# CAN-to-CAN.net
KiCad netlist of a schematic drawn in Altium Designer
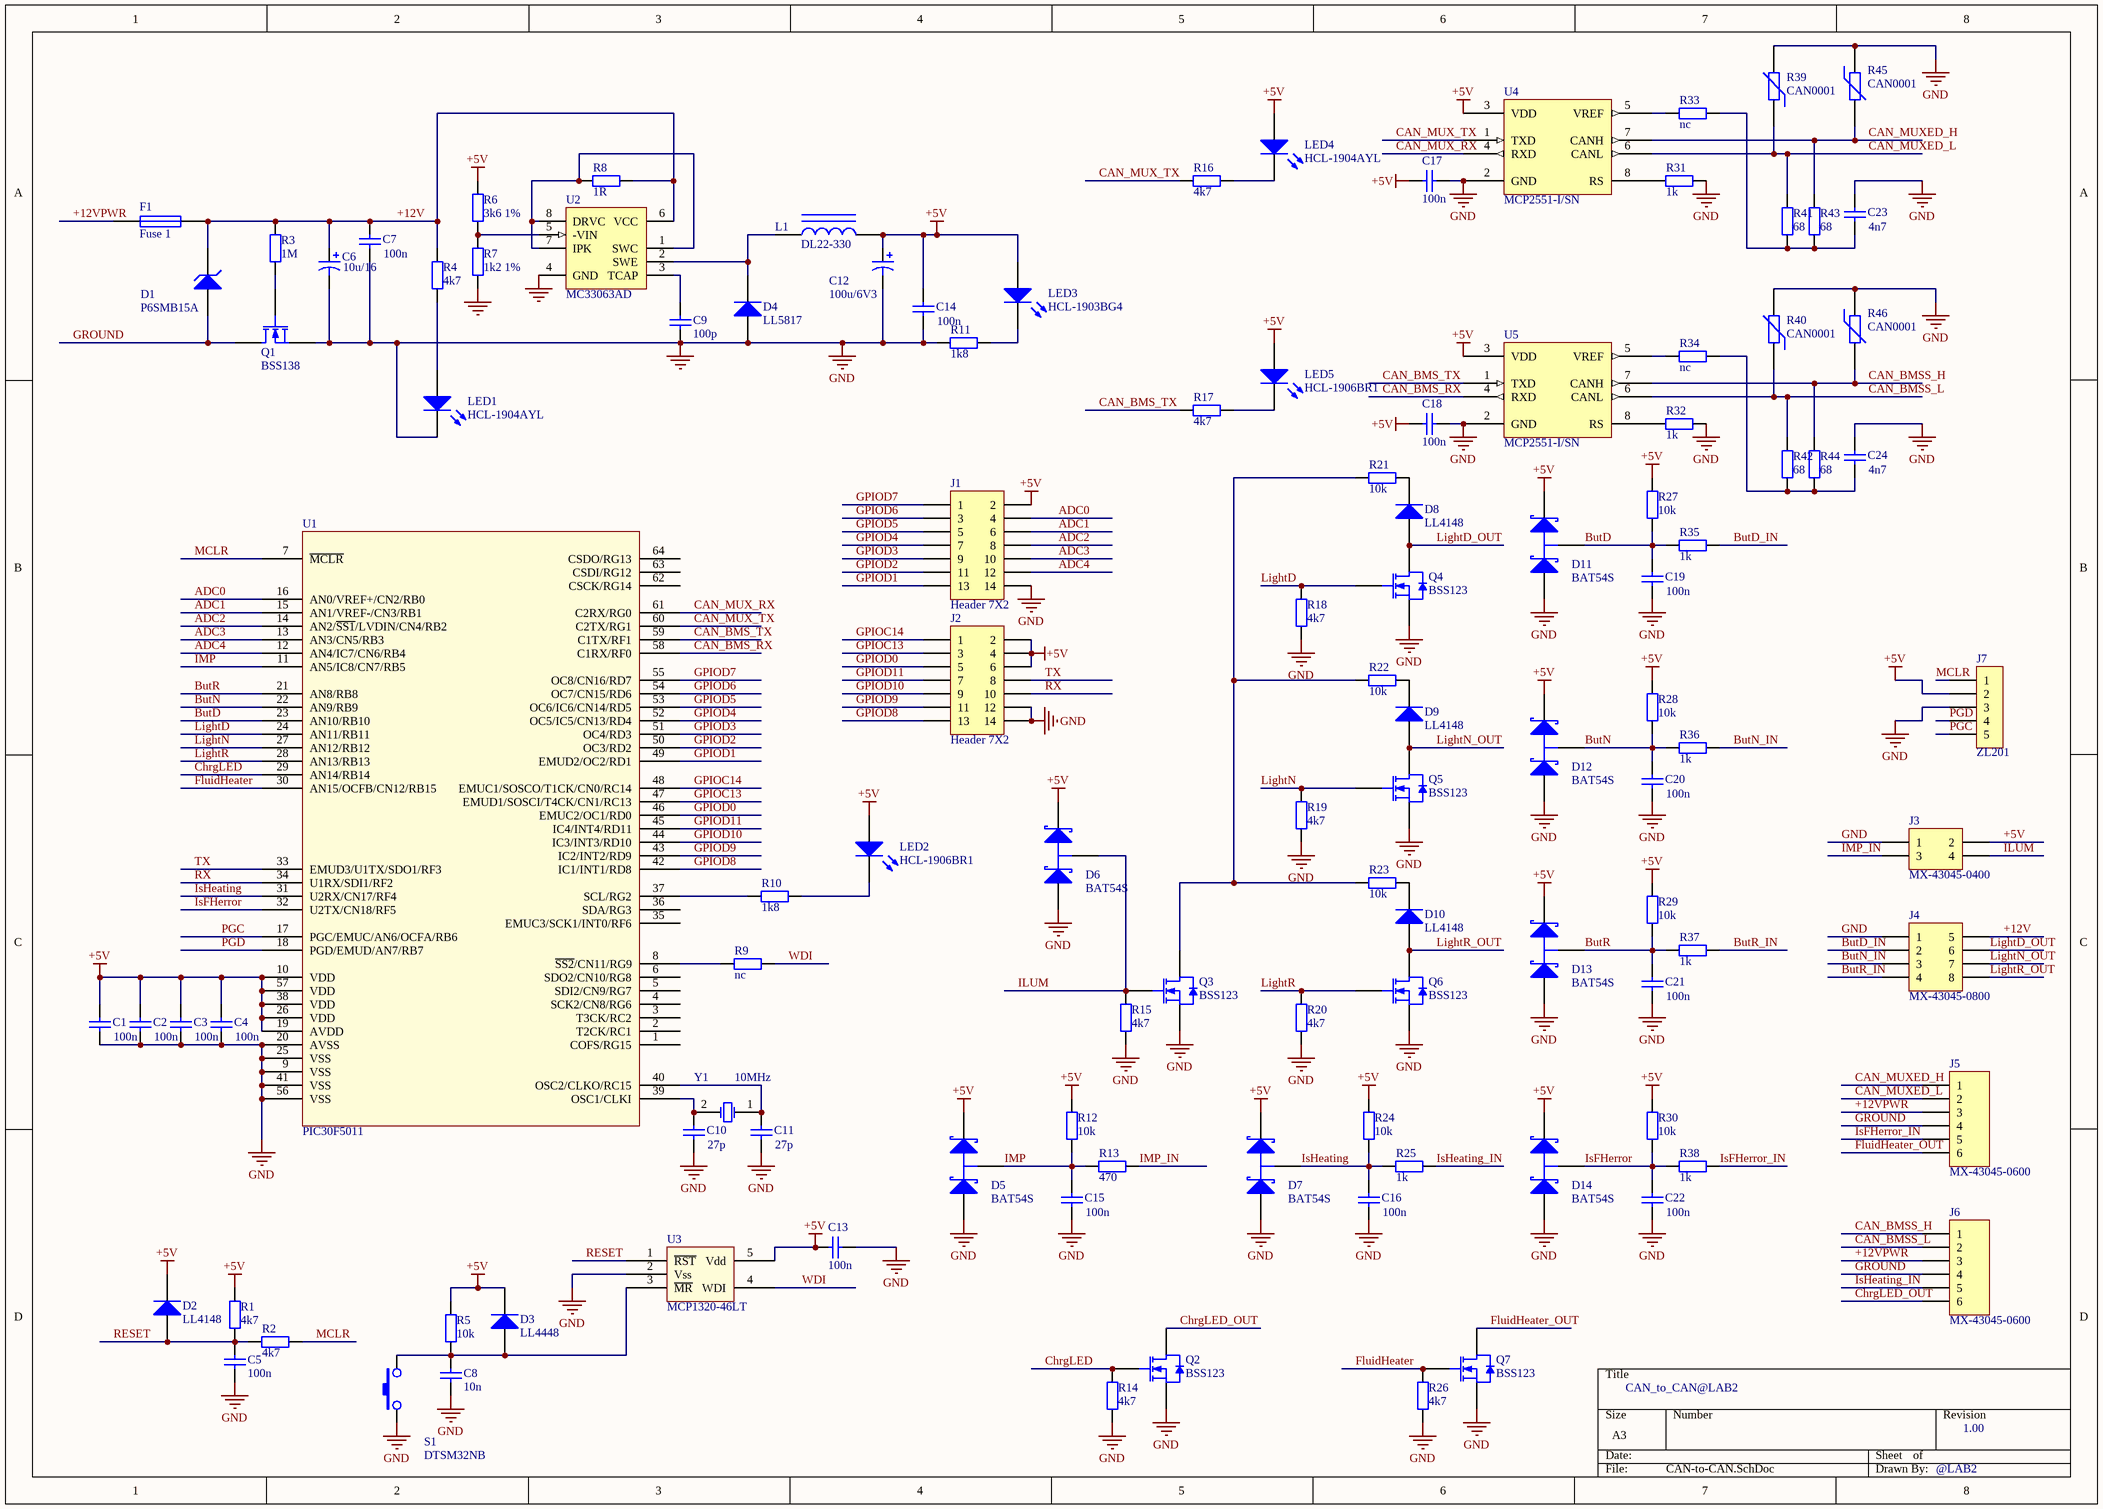
[diagram p0: CAN-to-CAN.SchDoc]

(export (version "E")
  (design (tool "Eeschema 10.0.6"))
  (components
    (comp (ref "C1")
      (value "100n")
      (footprint "0603")
      (description "Capacitor")
      (libsource (lib "Miscellaneous Devices") (part "Cap"))
    )
    (comp (ref "C2")
      (value "100n")
      (footprint "0603")
      (description "Capacitor")
      (libsource (lib "Miscellaneous Devices") (part "Cap"))
    )
    (comp (ref "C3")
      (value "100n")
      (footprint "0603")
      (description "Capacitor")
      (libsource (lib "Miscellaneous Devices") (part "Cap"))
    )
    (comp (ref "C4")
      (value "100n")
      (footprint "0603")
      (description "Capacitor")
      (libsource (lib "Miscellaneous Devices") (part "Cap"))
    )
    (comp (ref "C5")
      (value "100n")
      (footprint "0603")
      (description "Capacitor")
      (libsource (lib "Miscellaneous Devices") (part "Cap"))
    )
    (comp (ref "C6")
      (value "10u/16")
      (footprint "1608[0603]")
      (description "Polarized Capacitor (Radial)")
      (libsource (lib "Miscellaneous Devices") (part "Cap Pol1"))
    )
    (comp (ref "C7")
      (value "100n")
      (footprint "1812")
      (description "Capacitor")
      (libsource (lib "Miscellaneous Devices") (part "Cap"))
    )
    (comp (ref "C8")
      (value "10n")
      (footprint "0603")
      (description "Capacitor")
      (libsource (lib "Miscellaneous Devices") (part "Cap"))
    )
    (comp (ref "C9")
      (value "100p")
      (footprint "0603")
      (description "Capacitor")
      (libsource (lib "Miscellaneous Devices") (part "Cap"))
    )
    (comp (ref "C10")
      (value "27p")
      (footprint "0603")
      (description "Capacitor")
      (libsource (lib "Miscellaneous Devices") (part "Cap"))
    )
    (comp (ref "C11")
      (value "27p")
      (footprint "0603")
      (description "Capacitor")
      (libsource (lib "Miscellaneous Devices") (part "Cap"))
    )
    (comp (ref "C12")
      (value "100u/6V3")
      (footprint "0402")
      (description "Polarized Capacitor (Radial)")
      (libsource (lib "Miscellaneous Devices") (part "Cap Pol1"))
    )
    (comp (ref "C13")
      (value "100n")
      (footprint "0603")
      (description "Capacitor")
      (libsource (lib "Miscellaneous Devices") (part "Cap"))
    )
    (comp (ref "C14")
      (value "100n")
      (footprint "0603")
      (description "Capacitor")
      (libsource (lib "Miscellaneous Devices") (part "Cap"))
    )
    (comp (ref "C15")
      (value "100n")
      (footprint "0603")
      (description "Capacitor")
      (libsource (lib "Miscellaneous Devices") (part "Cap"))
    )
    (comp (ref "C16")
      (value "100n")
      (footprint "0603")
      (description "Capacitor")
      (libsource (lib "Miscellaneous Devices") (part "Cap"))
    )
    (comp (ref "C17")
      (value "100n")
      (footprint "0603")
      (description "Capacitor")
      (libsource (lib "Miscellaneous Devices") (part "Cap"))
    )
    (comp (ref "C18")
      (value "100n")
      (footprint "0603")
      (description "Capacitor")
      (libsource (lib "Miscellaneous Devices") (part "Cap"))
    )
    (comp (ref "C19")
      (value "100n")
      (footprint "0603")
      (description "Capacitor")
      (libsource (lib "Miscellaneous Devices") (part "Cap"))
    )
    (comp (ref "C20")
      (value "100n")
      (footprint "0603")
      (description "Capacitor")
      (libsource (lib "Miscellaneous Devices") (part "Cap"))
    )
    (comp (ref "C21")
      (value "100n")
      (footprint "0603")
      (description "Capacitor")
      (libsource (lib "Miscellaneous Devices") (part "Cap"))
    )
    (comp (ref "C22")
      (value "100n")
      (footprint "0603")
      (description "Capacitor")
      (libsource (lib "Miscellaneous Devices") (part "Cap"))
    )
    (comp (ref "C23")
      (value "4n7")
      (footprint "0603")
      (description "Capacitor")
      (libsource (lib "Miscellaneous Devices") (part "Cap"))
    )
    (comp (ref "C24")
      (value "4n7")
      (footprint "0603")
      (description "Capacitor")
      (libsource (lib "Miscellaneous Devices") (part "Cap"))
    )
    (comp (ref "D1")
      (value "P6SMB15A")
      (footprint "SMB")
      (description "Zener Diode")
      (libsource (lib "Miscellaneous Devices") (part "D Zener"))
    )
    (comp (ref "D2")
      (value "LL4148")
      (footprint "DIODE-0.4")
      (description "High Conductance Fast Diode")
      (libsource (lib "FSC Discrete Diode") (part "1N4148"))
    )
    (comp (ref "D3")
      (value "LL4448")
      (footprint "DIODE_SMC")
      (description "Default Diode")
      (libsource (lib "Miscellaneous Devices") (part "Diode"))
    )
    (comp (ref "D4")
      (value "LL5817")
      (footprint "DIODE-0.7")
      (description "High Conductance Fast Diode")
      (libsource (lib "FSC Discrete Diode") (part "1N4148"))
    )
    (comp (ref "D5")
      (value "BAT54S")
      (footprint "DO-35")
      (description "Schottky Barrier Double Diode")
      (libsource (lib "Philips Discrete Diode - Schottky") (part "BAT54S"))
    )
    (comp (ref "D6")
      (value "BAT54S")
      (footprint "DO-41")
      (description "Schottky Barrier Double Diode")
      (libsource (lib "Philips Discrete Diode - Schottky") (part "BAT54S"))
    )
    (comp (ref "D7")
      (value "BAT54S")
      (footprint "DO-204AL")
      (description "Schottky Barrier Double Diode")
      (libsource (lib "Philips Discrete Diode - Schottky") (part "BAT54S"))
    )
    (comp (ref "D8")
      (value "LL4148")
      (footprint "DO-201AD")
      (description "High Conductance Fast Diode")
      (libsource (lib "FSC Discrete Diode") (part "1N4148"))
    )
    (comp (ref "D9")
      (value "LL4148")
      (footprint "DIODE-0.4")
      (description "High Conductance Fast Diode")
      (libsource (lib "FSC Discrete Diode") (part "1N4148"))
    )
    (comp (ref "D10")
      (value "LL4148")
      (footprint "DO-7")
      (description "High Conductance Fast Diode")
      (libsource (lib "FSC Discrete Diode") (part "1N4148"))
    )
    (comp (ref "D11")
      (value "BAT54S")
      (footprint "DO-41")
      (description "Schottky Barrier Double Diode")
      (libsource (lib "Philips Discrete Diode - Schottky") (part "BAT54S"))
    )
    (comp (ref "D12")
      (value "BAT54S")
      (footprint "DO-201AD")
      (description "Schottky Barrier Double Diode")
      (libsource (lib "Philips Discrete Diode - Schottky") (part "BAT54S"))
    )
    (comp (ref "D13")
      (value "BAT54S")
      (footprint "DO-201AD")
      (description "Schottky Barrier Double Diode")
      (libsource (lib "Philips Discrete Diode - Schottky") (part "BAT54S"))
    )
    (comp (ref "D14")
      (value "BAT54S")
      (footprint "DO-41")
      (description "Schottky Barrier Double Diode")
      (libsource (lib "Philips Discrete Diode - Schottky") (part "BAT54S"))
    )
    (comp (ref "F1")
      (value "Fuse 1")
      (footprint "1812")
      (description "Fuse")
      (libsource (lib "Miscellaneous Devices") (part "Fuse 1"))
    )
    (comp (ref "J1")
      (value "Header 7X2")
      (footprint "HDR2X7")
      (description "Header, 7-Pin, Dual row")
      (libsource (lib "Miscellaneous Connectors") (part "Header 7X2"))
    )
    (comp (ref "J2")
      (value "Header 7X2")
      (footprint "HDR2X7")
      (description "Header, 7-Pin, Dual row")
      (libsource (lib "Miscellaneous Connectors") (part "Header 7X2"))
    )
    (comp (ref "J3")
      (value "MX-43045-0400")
      (footprint "SOT223_N")
      (description "Header, 2-Pin, Dual row")
      (libsource (lib "Miscellaneous Connectors") (part "Header 2X2"))
    )
    (comp (ref "J4")
      (value "MX-43045-0800")
      (footprint "DIP-8")
      (description "Header, 4-Pin, Dual row")
      (libsource (lib "Miscellaneous Connectors") (part "Header 4X2A"))
    )
    (comp (ref "J5")
      (value "MX-43045-0600")
      (footprint "DPDT-6")
      (description "Header, 6-Pin")
      (libsource (lib "Miscellaneous Connectors") (part "Header 6"))
    )
    (comp (ref "J6")
      (value "MX-43045-0600")
      (footprint "DPDT-6")
      (description "Header, 6-Pin")
      (libsource (lib "Miscellaneous Connectors") (part "Header 6"))
    )
    (comp (ref "J7")
      (value "ZL201")
      (footprint "HDR1X5")
      (description "Connector")
      (libsource (lib "*") (part "CON5"))
    )
    (comp (ref "L1")
      (value "DL22-330")
      (footprint "0603")
      (description "Magnetic-Core Inductor")
      (libsource (lib "Miscellaneous Devices") (part "Inductor Iron"))
    )
    (comp (ref "LED1")
      (value "HCL-1904AYL")
      (footprint "0603")
      (description "Typical BLUE SiC LED")
      (libsource (lib "Miscellaneous Devices") (part "LED3"))
    )
    (comp (ref "LED2")
      (value "HCL-1906BR1")
      (footprint "0603")
      (description "Typical BLUE SiC LED")
      (libsource (lib "Miscellaneous Devices") (part "LED3"))
    )
    (comp (ref "LED3")
      (value "HCL-1903BG4")
      (footprint "0603")
      (description "Typical BLUE SiC LED")
      (libsource (lib "Miscellaneous Devices") (part "LED3"))
    )
    (comp (ref "LED4")
      (value "HCL-1904AYL")
      (footprint "0603")
      (description "Typical BLUE SiC LED")
      (libsource (lib "Miscellaneous Devices") (part "LED3"))
    )
    (comp (ref "LED5")
      (value "HCL-1906BR1")
      (footprint "0603")
      (description "Typical BLUE SiC LED")
      (libsource (lib "Miscellaneous Devices") (part "LED3"))
    )
    (comp (ref "Q1")
      (value "BSS138")
      (footprint "SOT89L")
      (description "N-Channel Enhancement Mode Vertical DMOS FET")
      (libsource (lib "Zetex Discrete MOSFET") (part "BSS138"))
    )
    (comp (ref "Q2")
      (value "BSS123")
      (footprint "SOT23_M")
      (description "N-channel Enhancement Mode Vertical D-MOSFET")
      (libsource (lib "Philips Discrete MOSFET - Low Power") (part "BSS123"))
    )
    (comp (ref "Q3")
      (value "BSS123")
      (footprint "SOT23_M")
      (description "N-channel Enhancement Mode Vertical D-MOSFET")
      (libsource (lib "Philips Discrete MOSFET - Low Power") (part "BSS123"))
    )
    (comp (ref "Q4")
      (value "BSS123")
      (footprint "SOT89L")
      (description "N-channel Enhancement Mode Vertical D-MOSFET")
      (libsource (lib "Philips Discrete MOSFET - Low Power") (part "BSS123"))
    )
    (comp (ref "Q5")
      (value "BSS123")
      (footprint "DIP-P8")
      (description "N-channel Enhancement Mode Vertical D-MOSFET")
      (libsource (lib "Philips Discrete MOSFET - Low Power") (part "BSS123"))
    )
    (comp (ref "Q6")
      (value "BSS123")
      (footprint "DIODE_SMC")
      (description "N-channel Enhancement Mode Vertical D-MOSFET")
      (libsource (lib "Philips Discrete MOSFET - Low Power") (part "BSS123"))
    )
    (comp (ref "Q7")
      (value "BSS123")
      (footprint "SOT89N")
      (description "N-channel Enhancement Mode Vertical D-MOSFET")
      (libsource (lib "Philips Discrete MOSFET - Low Power") (part "BSS123"))
    )
    (comp (ref "R1")
      (value "4k7")
      (footprint "0603")
      (description "Resistor")
      (libsource (lib "Miscellaneous Devices") (part "Res2"))
    )
    (comp (ref "R2")
      (value "4k7")
      (footprint "0603")
      (description "Resistor")
      (libsource (lib "") (part "Res2_2"))
    )
    (comp (ref "R3")
      (value "1M")
      (footprint "6-0805_L")
      (description "Resistor")
      (libsource (lib "Miscellaneous Devices") (part "Res2"))
    )
    (comp (ref "R4")
      (value "4k7")
      (footprint "6-0805_N")
      (description "Resistor")
      (libsource (lib "Miscellaneous Devices") (part "Res2"))
    )
    (comp (ref "R5")
      (value "10k")
      (footprint "0603")
      (description "Resistor")
      (libsource (lib "") (part "Res2_3"))
    )
    (comp (ref "R6")
      (value "3k6 1%")
      (footprint "0603")
      (description "Resistor")
      (libsource (lib "Miscellaneous Devices") (part "Res2"))
    )
    (comp (ref "R7")
      (value "1k2 1%")
      (footprint "0603")
      (description "Resistor")
      (libsource (lib "") (part "Res2_3"))
    )
    (comp (ref "R8")
      (value "1R")
      (footprint "6-0805_L")
      (description "Resistor")
      (libsource (lib "") (part "Res2_1"))
    )
    (comp (ref "R9")
      (value "nc")
      (footprint "0603")
      (description "Resistor")
      (libsource (lib "") (part "Res2_2"))
    )
    (comp (ref "R10")
      (value "1k8")
      (footprint "0603")
      (description "Resistor")
      (libsource (lib "") (part "Res2_2"))
    )
    (comp (ref "R11")
      (value "1k8")
      (footprint "0603")
      (description "Resistor")
      (libsource (lib "") (part "Res2_2"))
    )
    (comp (ref "R12")
      (value "10k")
      (footprint "0603")
      (description "Resistor")
      (libsource (lib "Miscellaneous Devices") (part "Res2"))
    )
    (comp (ref "R13")
      (value "470")
      (footprint "0603")
      (description "Resistor")
      (libsource (lib "") (part "Res2_2"))
    )
    (comp (ref "R14")
      (value "4k7")
      (footprint "0603")
      (description "Resistor")
      (libsource (lib "Miscellaneous Devices") (part "Res2"))
    )
    (comp (ref "R15")
      (value "4k7")
      (footprint "0603")
      (description "Resistor")
      (libsource (lib "Miscellaneous Devices") (part "Res2"))
    )
    (comp (ref "R16")
      (value "4k7")
      (footprint "0603")
      (description "Resistor")
      (libsource (lib "") (part "Res2_2"))
    )
    (comp (ref "R17")
      (value "4k7")
      (footprint "0603")
      (description "Resistor")
      (libsource (lib "") (part "Res2_2"))
    )
    (comp (ref "R18")
      (value "4k7")
      (footprint "0603")
      (description "Resistor")
      (libsource (lib "Miscellaneous Devices") (part "Res2"))
    )
    (comp (ref "R19")
      (value "4k7")
      (footprint "0603")
      (description "Resistor")
      (libsource (lib "Miscellaneous Devices") (part "Res2"))
    )
    (comp (ref "R20")
      (value "4k7")
      (footprint "0603")
      (description "Resistor")
      (libsource (lib "Miscellaneous Devices") (part "Res2"))
    )
    (comp (ref "R21")
      (value "10k")
      (footprint "0603")
      (description "Resistor")
      (libsource (lib "") (part "Res2_1"))
    )
    (comp (ref "R22")
      (value "10k")
      (footprint "0603")
      (description "Resistor")
      (libsource (lib "") (part "Res2_1"))
    )
    (comp (ref "R23")
      (value "10k")
      (footprint "0603")
      (description "Resistor")
      (libsource (lib "") (part "Res2_1"))
    )
    (comp (ref "R24")
      (value "10k")
      (footprint "0603")
      (description "Resistor")
      (libsource (lib "Miscellaneous Devices") (part "Res2"))
    )
    (comp (ref "R25")
      (value "1k")
      (footprint "0603")
      (description "Resistor")
      (libsource (lib "") (part "Res2_2"))
    )
    (comp (ref "R26")
      (value "4k7")
      (footprint "0603")
      (description "Resistor")
      (libsource (lib "Miscellaneous Devices") (part "Res2"))
    )
    (comp (ref "R27")
      (value "10k")
      (footprint "0603")
      (description "Resistor")
      (libsource (lib "Miscellaneous Devices") (part "Res2"))
    )
    (comp (ref "R28")
      (value "10k")
      (footprint "0603")
      (description "Resistor")
      (libsource (lib "Miscellaneous Devices") (part "Res2"))
    )
    (comp (ref "R29")
      (value "10k")
      (footprint "0603")
      (description "Resistor")
      (libsource (lib "Miscellaneous Devices") (part "Res2"))
    )
    (comp (ref "R30")
      (value "10k")
      (footprint "0603")
      (description "Resistor")
      (libsource (lib "Miscellaneous Devices") (part "Res2"))
    )
    (comp (ref "R31")
      (value "1k")
      (footprint "0603")
      (description "Resistor")
      (libsource (lib "") (part "Res2_1"))
    )
    (comp (ref "R32")
      (value "1k")
      (footprint "0603")
      (description "Resistor")
      (libsource (lib "") (part "Res2_1"))
    )
    (comp (ref "R33")
      (value "nc")
      (footprint "0603")
      (description "Resistor")
      (libsource (lib "") (part "Res2_1"))
    )
    (comp (ref "R34")
      (value "nc")
      (footprint "0603")
      (description "Resistor")
      (libsource (lib "") (part "Res2_1"))
    )
    (comp (ref "R35")
      (value "1k")
      (footprint "0603")
      (description "Resistor")
      (libsource (lib "") (part "Res2_2"))
    )
    (comp (ref "R36")
      (value "1k")
      (footprint "0603")
      (description "Resistor")
      (libsource (lib "") (part "Res2_2"))
    )
    (comp (ref "R37")
      (value "1k")
      (footprint "0603")
      (description "Resistor")
      (libsource (lib "") (part "Res2_2"))
    )
    (comp (ref "R38")
      (value "1k")
      (footprint "0603")
      (description "Resistor")
      (libsource (lib "") (part "Res2_2"))
    )
    (comp (ref "R39")
      (value "CAN0001")
      (footprint "0603")
      (description "Varistor (Voltage-Sensitive Resistor)")
      (libsource (lib "Miscellaneous Devices") (part "Res Varistor"))
    )
    (comp (ref "R40")
      (value "CAN0001")
      (footprint "0603")
      (description "Varistor (Voltage-Sensitive Resistor)")
      (libsource (lib "Miscellaneous Devices") (part "Res Varistor"))
    )
    (comp (ref "R41")
      (value "68")
      (footprint "0603")
      (description "Resistor")
      (libsource (lib "Miscellaneous Devices") (part "Res2"))
    )
    (comp (ref "R42")
      (value "68")
      (footprint "0603")
      (description "Resistor")
      (libsource (lib "Miscellaneous Devices") (part "Res2"))
    )
    (comp (ref "R43")
      (value "68")
      (footprint "0603")
      (description "Resistor")
      (libsource (lib "Miscellaneous Devices") (part "Res2"))
    )
    (comp (ref "R44")
      (value "68")
      (footprint "0603")
      (description "Resistor")
      (libsource (lib "Miscellaneous Devices") (part "Res2"))
    )
    (comp (ref "R45")
      (value "CAN0001")
      (footprint "0603")
      (description "Varistor (Voltage-Sensitive Resistor)")
      (libsource (lib "Miscellaneous Devices") (part "Res Varistor"))
    )
    (comp (ref "R46")
      (value "CAN0001")
      (footprint "0603")
      (description "Varistor (Voltage-Sensitive Resistor)")
      (libsource (lib "Miscellaneous Devices") (part "Res Varistor"))
    )
    (comp (ref "S1")
      (value "DTSM32NB")
      (footprint "PIN-W2/E2.8")
      (description "Switch PushButton")
      (libsource (lib "*") (part "PUSHB"))
    )
    (comp (ref "U1")
      (value "PIC30F5011")
      (footprint "TQFP-64_L")
      (description "PIC30F5011 - Up")
      (libsource (lib "AD Microcontroller ARM") (part "PIC30F5011"))
    )
    (comp (ref "U2")
      (value "MC33063AD")
      (footprint "SO8_N")
      (description "DC-to-DC Converter Control Circuit")
      (libsource (lib "Motorola Power Mgt DC-DC Converter") (part "MC33063AD"))
    )
    (comp (ref "U3")
      (value "MCP1320-46LT")
      (footprint "MODULE5B")
      (libsource (lib "X-Tro's Misc") (part "MCP1320"))
    )
    (comp (ref "U4")
      (value "MCP2551-I/SN")
      (footprint "DB008_L")
      (description "High Speed CAN Transceiver, 8-Pin Plastic SOIC, Industrial Grade")
      (libsource (lib "Microchip Interface Line Transceiver") (part "MCP2551-I/SN"))
    )
    (comp (ref "U5")
      (value "MCP2551-I/SN")
      (footprint "DIP-8")
      (description "High Speed CAN Transceiver, 8-Pin Plastic SOIC, Industrial Grade")
      (libsource (lib "Microchip Interface Line Transceiver") (part "MCP2551-I/SN"))
    )
    (comp (ref "Y1")
      (value "10MHz")
      (footprint "SPST-2")
      (description "Crystal Oscillator")
      (libsource (lib "Miscellaneous Devices") (part "XTAL"))
    )
  )
  (nets
    (net (code "1") (name "+5V") (class "Default")
      (node (ref "C1") (pin "1") (pinfunction "1_1") (pintype "passive"))
      (node (ref "C12") (pin "1") (pinfunction "1_1") (pintype "passive"))
      (node (ref "C13") (pin "1") (pinfunction "1_1") (pintype "passive"))
      (node (ref "C14") (pin "1") (pinfunction "1_1") (pintype "passive"))
      (node (ref "C17") (pin "1") (pinfunction "1_1") (pintype "passive"))
      (node (ref "C18") (pin "1") (pinfunction "1_1") (pintype "passive"))
      (node (ref "C2") (pin "1") (pinfunction "1_1") (pintype "passive"))
      (node (ref "C3") (pin "1") (pinfunction "1_1") (pintype "passive"))
      (node (ref "C4") (pin "1") (pinfunction "1_1") (pintype "passive"))
      (node (ref "D11") (pin "2") (pinfunction "K_2") (pintype "passive"))
      (node (ref "D12") (pin "2") (pinfunction "K_2") (pintype "passive"))
      (node (ref "D13") (pin "2") (pinfunction "K_2") (pintype "passive"))
      (node (ref "D14") (pin "2") (pinfunction "K_2") (pintype "passive"))
      (node (ref "D2") (pin "2") (pinfunction "K_2") (pintype "passive"))
      (node (ref "D3") (pin "2") (pinfunction "K_2") (pintype "passive"))
      (node (ref "D5") (pin "2") (pinfunction "K_2") (pintype "passive"))
      (node (ref "D6") (pin "2") (pinfunction "K_2") (pintype "passive"))
      (node (ref "D7") (pin "2") (pinfunction "K_2") (pintype "passive"))
      (node (ref "J1") (pin "2") (pinfunction "2_2") (pintype "passive"))
      (node (ref "J2") (pin "2") (pinfunction "2_2") (pintype "passive"))
      (node (ref "J2") (pin "4") (pinfunction "4_4") (pintype "passive"))
      (node (ref "J2") (pin "6") (pinfunction "6_6") (pintype "passive"))
      (node (ref "J3") (pin "2") (pinfunction "2_2") (pintype "passive"))
      (node (ref "J7") (pin "2") (pinfunction "2_2") (pintype "passive"))
      (node (ref "L1") (pin "2") (pinfunction "2_2") (pintype "passive"))
      (node (ref "LED2") (pin "1") (pinfunction "A_1") (pintype "passive"))
      (node (ref "LED3") (pin "1") (pinfunction "A_1") (pintype "passive"))
      (node (ref "LED4") (pin "1") (pinfunction "A_1") (pintype "passive"))
      (node (ref "LED5") (pin "1") (pinfunction "A_1") (pintype "passive"))
      (node (ref "R1") (pin "1") (pinfunction "1_1") (pintype "passive"))
      (node (ref "R12") (pin "1") (pinfunction "1_1") (pintype "passive"))
      (node (ref "R24") (pin "1") (pinfunction "1_1") (pintype "passive"))
      (node (ref "R27") (pin "1") (pinfunction "1_1") (pintype "passive"))
      (node (ref "R28") (pin "1") (pinfunction "1_1") (pintype "passive"))
      (node (ref "R29") (pin "1") (pinfunction "1_1") (pintype "passive"))
      (node (ref "R30") (pin "1") (pinfunction "1_1") (pintype "passive"))
      (node (ref "R5") (pin "2") (pinfunction "2_2") (pintype "passive"))
      (node (ref "R6") (pin "1") (pinfunction "1_1") (pintype "passive"))
      (node (ref "U1") (pin "10") (pinfunction "VDD_10") (pintype "passive"))
      (node (ref "U1") (pin "19") (pinfunction "AVDD_19") (pintype "passive"))
      (node (ref "U1") (pin "26") (pinfunction "VDD_26") (pintype "passive"))
      (node (ref "U1") (pin "38") (pinfunction "VDD_38") (pintype "passive"))
      (node (ref "U1") (pin "57") (pinfunction "VDD_57") (pintype "passive"))
      (node (ref "U3") (pin "5") (pinfunction "Vdd_5") (pintype "passive"))
      (node (ref "U4") (pin "3") (pinfunction "VDD_3") (pintype "power_in"))
      (node (ref "U5") (pin "3") (pinfunction "VDD_3") (pintype "power_in"))
    )
    (net (code "2") (name "/+12V") (class "Default")
      (node (ref "C6") (pin "1") (pinfunction "1_1") (pintype "passive"))
      (node (ref "C7") (pin "1") (pinfunction "1_1") (pintype "passive"))
      (node (ref "D1") (pin "2") (pinfunction "K_2") (pintype "passive"))
      (node (ref "F1") (pin "2") (pinfunction "2_2") (pintype "passive"))
      (node (ref "J4") (pin "5") (pinfunction "5_5") (pintype "passive"))
      (node (ref "R3") (pin "1") (pinfunction "1_1") (pintype "passive"))
      (node (ref "R4") (pin "1") (pinfunction "1_1") (pintype "passive"))
      (node (ref "R8") (pin "2") (pinfunction "2_2") (pintype "passive"))
      (node (ref "U2") (pin "6") (pinfunction "VCC_6") (pintype "power_in"))
    )
    (net (code "3") (name "/+12VPWR") (class "Default")
      (node (ref "F1") (pin "1") (pinfunction "1_1") (pintype "passive"))
      (node (ref "J5") (pin "3") (pinfunction "3_3") (pintype "passive"))
      (node (ref "J6") (pin "3") (pinfunction "3_3") (pintype "passive"))
    )
    (net (code "4") (name "/ADC0") (class "Default")
      (node (ref "J1") (pin "4") (pinfunction "4_4") (pintype "passive"))
      (node (ref "U1") (pin "16") (pinfunction "AN0/VREF+/CN2/RB0_16") (pintype "passive"))
    )
    (net (code "5") (name "/ADC1") (class "Default")
      (node (ref "J1") (pin "6") (pinfunction "6_6") (pintype "passive"))
      (node (ref "U1") (pin "15") (pinfunction "AN1/VREF-/CN3/RB1_15") (pintype "passive"))
    )
    (net (code "6") (name "/ADC2") (class "Default")
      (node (ref "J1") (pin "8") (pinfunction "8_8") (pintype "passive"))
      (node (ref "U1") (pin "14") (pinfunction "AN2/~{SS1}/LVDIN/CN4/RB2_14") (pintype "passive"))
    )
    (net (code "7") (name "/ADC3") (class "Default")
      (node (ref "J1") (pin "10") (pinfunction "10_10") (pintype "passive"))
      (node (ref "U1") (pin "13") (pinfunction "AN3/CN5/RB3_13") (pintype "passive"))
    )
    (net (code "8") (name "/ADC4") (class "Default")
      (node (ref "J1") (pin "12") (pinfunction "12_12") (pintype "passive"))
      (node (ref "U1") (pin "12") (pinfunction "AN4/IC7/CN6/RB4_12") (pintype "passive"))
    )
    (net (code "9") (name "/ButD") (class "Default")
      (node (ref "C19") (pin "1") (pinfunction "1_1") (pintype "passive"))
      (node (ref "D11") (pin "3") (pinfunction "C_3") (pintype "passive"))
      (node (ref "R27") (pin "2") (pinfunction "2_2") (pintype "passive"))
      (node (ref "R35") (pin "2") (pinfunction "2_2") (pintype "passive"))
      (node (ref "U1") (pin "23") (pinfunction "AN10/RB10_23") (pintype "passive"))
    )
    (net (code "10") (name "/ButD_IN") (class "Default")
      (node (ref "J4") (pin "2") (pinfunction "2_2") (pintype "passive"))
      (node (ref "R35") (pin "1") (pinfunction "1_1") (pintype "passive"))
    )
    (net (code "11") (name "/ButN") (class "Default")
      (node (ref "C20") (pin "1") (pinfunction "1_1") (pintype "passive"))
      (node (ref "D12") (pin "3") (pinfunction "C_3") (pintype "passive"))
      (node (ref "R28") (pin "2") (pinfunction "2_2") (pintype "passive"))
      (node (ref "R36") (pin "2") (pinfunction "2_2") (pintype "passive"))
      (node (ref "U1") (pin "22") (pinfunction "AN9/RB9_22") (pintype "passive"))
    )
    (net (code "12") (name "/ButN_IN") (class "Default")
      (node (ref "J4") (pin "3") (pinfunction "3_3") (pintype "passive"))
      (node (ref "R36") (pin "1") (pinfunction "1_1") (pintype "passive"))
    )
    (net (code "13") (name "/ButR") (class "Default")
      (node (ref "C21") (pin "1") (pinfunction "1_1") (pintype "passive"))
      (node (ref "D13") (pin "3") (pinfunction "C_3") (pintype "passive"))
      (node (ref "R29") (pin "2") (pinfunction "2_2") (pintype "passive"))
      (node (ref "R37") (pin "2") (pinfunction "2_2") (pintype "passive"))
      (node (ref "U1") (pin "21") (pinfunction "AN8/RB8_21") (pintype "passive"))
    )
    (net (code "14") (name "/ButR_IN") (class "Default")
      (node (ref "J4") (pin "4") (pinfunction "4_4") (pintype "passive"))
      (node (ref "R37") (pin "1") (pinfunction "1_1") (pintype "passive"))
    )
    (net (code "15") (name "/CAN_BMSS_H") (class "Default")
      (node (ref "J6") (pin "1") (pinfunction "1_1") (pintype "passive"))
      (node (ref "R44") (pin "1") (pinfunction "1_1") (pintype "passive"))
      (node (ref "R46") (pin "2") (pinfunction "2_2") (pintype "passive"))
      (node (ref "U5") (pin "7") (pinfunction "CANH_7") (pintype "output"))
    )
    (net (code "16") (name "/CAN_BMSS_L") (class "Default")
      (node (ref "J6") (pin "2") (pinfunction "2_2") (pintype "passive"))
      (node (ref "R40") (pin "1") (pinfunction "1_1") (pintype "passive"))
      (node (ref "R42") (pin "1") (pinfunction "1_1") (pintype "passive"))
      (node (ref "U5") (pin "6") (pinfunction "CANL_6") (pintype "output"))
    )
    (net (code "17") (name "/CAN_BMS_RX") (class "Default")
      (node (ref "U1") (pin "58") (pinfunction "C1RX/RF0_58") (pintype "passive"))
      (node (ref "U5") (pin "4") (pinfunction "RXD_4") (pintype "output"))
    )
    (net (code "18") (name "/CAN_BMS_TX") (class "Default")
      (node (ref "R17") (pin "2") (pinfunction "2_2") (pintype "passive"))
      (node (ref "U1") (pin "59") (pinfunction "C1TX/RF1_59") (pintype "passive"))
      (node (ref "U5") (pin "1") (pinfunction "TXD_1") (pintype "input"))
    )
    (net (code "19") (name "/CAN_MUXED_H") (class "Default")
      (node (ref "J5") (pin "1") (pinfunction "1_1") (pintype "passive"))
      (node (ref "R43") (pin "1") (pinfunction "1_1") (pintype "passive"))
      (node (ref "R45") (pin "2") (pinfunction "2_2") (pintype "passive"))
      (node (ref "U4") (pin "7") (pinfunction "CANH_7") (pintype "output"))
    )
    (net (code "20") (name "/CAN_MUXED_L") (class "Default")
      (node (ref "J5") (pin "2") (pinfunction "2_2") (pintype "passive"))
      (node (ref "R39") (pin "1") (pinfunction "1_1") (pintype "passive"))
      (node (ref "R41") (pin "1") (pinfunction "1_1") (pintype "passive"))
      (node (ref "U4") (pin "6") (pinfunction "CANL_6") (pintype "output"))
    )
    (net (code "21") (name "/CAN_MUX_RX") (class "Default")
      (node (ref "U1") (pin "61") (pinfunction "C2RX/RG0_61") (pintype "passive"))
      (node (ref "U4") (pin "4") (pinfunction "RXD_4") (pintype "output"))
    )
    (net (code "22") (name "/CAN_MUX_TX") (class "Default")
      (node (ref "R16") (pin "2") (pinfunction "2_2") (pintype "passive"))
      (node (ref "U1") (pin "60") (pinfunction "C2TX/RG1_60") (pintype "passive"))
      (node (ref "U4") (pin "1") (pinfunction "TXD_1") (pintype "input"))
    )
    (net (code "23") (name "/ChrgLED") (class "Default")
      (node (ref "Q2") (pin "3") (pinfunction "G_3") (pintype "passive"))
      (node (ref "R14") (pin "1") (pinfunction "1_1") (pintype "passive"))
      (node (ref "U1") (pin "29") (pinfunction "AN14/RB14_29") (pintype "passive"))
    )
    (net (code "24") (name "/ChrgLED_OUT") (class "Default")
      (node (ref "J6") (pin "6") (pinfunction "6_6") (pintype "passive"))
      (node (ref "Q2") (pin "1") (pinfunction "D_1") (pintype "passive"))
    )
    (net (code "25") (name "/FluidHeater") (class "Default")
      (node (ref "Q7") (pin "3") (pinfunction "G_3") (pintype "passive"))
      (node (ref "R26") (pin "1") (pinfunction "1_1") (pintype "passive"))
      (node (ref "U1") (pin "30") (pinfunction "AN15/OCFB/CN12/RB15_30") (pintype "passive"))
    )
    (net (code "26") (name "/FluidHeater_OUT") (class "Default")
      (node (ref "J5") (pin "6") (pinfunction "6_6") (pintype "passive"))
      (node (ref "Q7") (pin "1") (pinfunction "D_1") (pintype "passive"))
    )
    (net (code "27") (name "/GPIOC13") (class "Default")
      (node (ref "J2") (pin "3") (pinfunction "3_3") (pintype "passive"))
      (node (ref "U1") (pin "47") (pinfunction "EMUD1/SOSCI/T4CK/CN1/RC13_47") (pintype "passive"))
    )
    (net (code "28") (name "/GPIOC14") (class "Default")
      (node (ref "J2") (pin "1") (pinfunction "1_1") (pintype "passive"))
      (node (ref "U1") (pin "48") (pinfunction "EMUC1/SOSCO/T1CK/CN0/RC14_48") (pintype "passive"))
    )
    (net (code "29") (name "/GPIOD0") (class "Default")
      (node (ref "J2") (pin "5") (pinfunction "5_5") (pintype "passive"))
      (node (ref "U1") (pin "46") (pinfunction "EMUC2/OC1/RD0_46") (pintype "passive"))
    )
    (net (code "30") (name "/GPIOD1") (class "Default")
      (node (ref "J1") (pin "13") (pinfunction "13_13") (pintype "passive"))
      (node (ref "U1") (pin "49") (pinfunction "EMUD2/OC2/RD1_49") (pintype "passive"))
    )
    (net (code "31") (name "/GPIOD2") (class "Default")
      (node (ref "J1") (pin "11") (pinfunction "11_11") (pintype "passive"))
      (node (ref "U1") (pin "50") (pinfunction "OC3/RD2_50") (pintype "passive"))
    )
    (net (code "32") (name "/GPIOD3") (class "Default")
      (node (ref "J1") (pin "9") (pinfunction "9_9") (pintype "passive"))
      (node (ref "U1") (pin "51") (pinfunction "OC4/RD3_51") (pintype "passive"))
    )
    (net (code "33") (name "/GPIOD4") (class "Default")
      (node (ref "J1") (pin "7") (pinfunction "7_7") (pintype "passive"))
      (node (ref "U1") (pin "52") (pinfunction "OC5/IC5/CN13/RD4_52") (pintype "passive"))
    )
    (net (code "34") (name "/GPIOD5") (class "Default")
      (node (ref "J1") (pin "5") (pinfunction "5_5") (pintype "passive"))
      (node (ref "U1") (pin "53") (pinfunction "OC6/IC6/CN14/RD5_53") (pintype "passive"))
    )
    (net (code "35") (name "/GPIOD6") (class "Default")
      (node (ref "J1") (pin "3") (pinfunction "3_3") (pintype "passive"))
      (node (ref "U1") (pin "54") (pinfunction "OC7/CN15/RD6_54") (pintype "passive"))
    )
    (net (code "36") (name "/GPIOD7") (class "Default")
      (node (ref "J1") (pin "1") (pinfunction "1_1") (pintype "passive"))
      (node (ref "U1") (pin "55") (pinfunction "OC8/CN16/RD7_55") (pintype "passive"))
    )
    (net (code "37") (name "/GPIOD8") (class "Default")
      (node (ref "J2") (pin "13") (pinfunction "13_13") (pintype "passive"))
      (node (ref "U1") (pin "42") (pinfunction "IC1/INT1/RD8_42") (pintype "passive"))
    )
    (net (code "38") (name "/GPIOD9") (class "Default")
      (node (ref "J2") (pin "11") (pinfunction "11_11") (pintype "passive"))
      (node (ref "U1") (pin "43") (pinfunction "IC2/INT2/RD9_43") (pintype "passive"))
    )
    (net (code "39") (name "/GPIOD10") (class "Default")
      (node (ref "J2") (pin "9") (pinfunction "9_9") (pintype "passive"))
      (node (ref "U1") (pin "44") (pinfunction "IC3/INT3/RD10_44") (pintype "passive"))
    )
    (net (code "40") (name "/GPIOD11") (class "Default")
      (node (ref "J2") (pin "7") (pinfunction "7_7") (pintype "passive"))
      (node (ref "U1") (pin "45") (pinfunction "IC4/INT4/RD11_45") (pintype "passive"))
    )
    (net (code "41") (name "/GROUND") (class "Default")
      (node (ref "D1") (pin "1") (pinfunction "A_1") (pintype "passive"))
      (node (ref "J5") (pin "4") (pinfunction "4_4") (pintype "passive"))
      (node (ref "J6") (pin "4") (pinfunction "4_4") (pintype "passive"))
      (node (ref "Q1") (pin "1") (pinfunction "D_1") (pintype "passive"))
    )
    (net (code "42") (name "/ILUM") (class "Default")
      (node (ref "D6") (pin "3") (pinfunction "C_3") (pintype "passive"))
      (node (ref "J3") (pin "4") (pinfunction "4_4") (pintype "passive"))
      (node (ref "Q3") (pin "3") (pinfunction "G_3") (pintype "passive"))
      (node (ref "R15") (pin "1") (pinfunction "1_1") (pintype "passive"))
    )
    (net (code "43") (name "/IMP") (class "Default")
      (node (ref "C15") (pin "1") (pinfunction "1_1") (pintype "passive"))
      (node (ref "D5") (pin "3") (pinfunction "C_3") (pintype "passive"))
      (node (ref "R12") (pin "2") (pinfunction "2_2") (pintype "passive"))
      (node (ref "R13") (pin "2") (pinfunction "2_2") (pintype "passive"))
      (node (ref "U1") (pin "11") (pinfunction "AN5/IC8/CN7/RB5_11") (pintype "passive"))
    )
    (net (code "44") (name "/IMP_IN") (class "Default")
      (node (ref "J3") (pin "3") (pinfunction "3_3") (pintype "passive"))
      (node (ref "R13") (pin "1") (pinfunction "1_1") (pintype "passive"))
    )
    (net (code "45") (name "/IsFHerror") (class "Default")
      (node (ref "C22") (pin "1") (pinfunction "1_1") (pintype "passive"))
      (node (ref "D14") (pin "3") (pinfunction "C_3") (pintype "passive"))
      (node (ref "R30") (pin "2") (pinfunction "2_2") (pintype "passive"))
      (node (ref "R38") (pin "2") (pinfunction "2_2") (pintype "passive"))
      (node (ref "U1") (pin "32") (pinfunction "U2TX/CN18/RF5_32") (pintype "passive"))
    )
    (net (code "46") (name "/IsFHerror_IN") (class "Default")
      (node (ref "J5") (pin "5") (pinfunction "5_5") (pintype "passive"))
      (node (ref "R38") (pin "1") (pinfunction "1_1") (pintype "passive"))
    )
    (net (code "47") (name "/IsHeating") (class "Default")
      (node (ref "C16") (pin "1") (pinfunction "1_1") (pintype "passive"))
      (node (ref "D7") (pin "3") (pinfunction "C_3") (pintype "passive"))
      (node (ref "R24") (pin "2") (pinfunction "2_2") (pintype "passive"))
      (node (ref "R25") (pin "2") (pinfunction "2_2") (pintype "passive"))
      (node (ref "U1") (pin "31") (pinfunction "U2RX/CN17/RF4_31") (pintype "passive"))
    )
    (net (code "48") (name "/IsHeating_IN") (class "Default")
      (node (ref "J6") (pin "5") (pinfunction "5_5") (pintype "passive"))
      (node (ref "R25") (pin "1") (pinfunction "1_1") (pintype "passive"))
    )
    (net (code "49") (name "/LightD") (class "Default")
      (node (ref "Q4") (pin "3") (pinfunction "G_3") (pintype "passive"))
      (node (ref "R18") (pin "1") (pinfunction "1_1") (pintype "passive"))
      (node (ref "U1") (pin "24") (pinfunction "AN11/RB11_24") (pintype "passive"))
    )
    (net (code "50") (name "/LightD_OUT") (class "Default")
      (node (ref "D8") (pin "1") (pinfunction "A_1") (pintype "passive"))
      (node (ref "J4") (pin "6") (pinfunction "6_6") (pintype "passive"))
      (node (ref "Q4") (pin "1") (pinfunction "D_1") (pintype "passive"))
    )
    (net (code "51") (name "/LightN") (class "Default")
      (node (ref "Q5") (pin "3") (pinfunction "G_3") (pintype "passive"))
      (node (ref "R19") (pin "1") (pinfunction "1_1") (pintype "passive"))
      (node (ref "U1") (pin "27") (pinfunction "AN12/RB12_27") (pintype "passive"))
    )
    (net (code "52") (name "/LightN_OUT") (class "Default")
      (node (ref "D9") (pin "1") (pinfunction "A_1") (pintype "passive"))
      (node (ref "J4") (pin "7") (pinfunction "7_7") (pintype "passive"))
      (node (ref "Q5") (pin "1") (pinfunction "D_1") (pintype "passive"))
    )
    (net (code "53") (name "/LightR") (class "Default")
      (node (ref "Q6") (pin "3") (pinfunction "G_3") (pintype "passive"))
      (node (ref "R20") (pin "1") (pinfunction "1_1") (pintype "passive"))
      (node (ref "U1") (pin "28") (pinfunction "AN13/RB13_28") (pintype "passive"))
    )
    (net (code "54") (name "/LightR_OUT") (class "Default")
      (node (ref "D10") (pin "1") (pinfunction "A_1") (pintype "passive"))
      (node (ref "J4") (pin "8") (pinfunction "8_8") (pintype "passive"))
      (node (ref "Q6") (pin "1") (pinfunction "D_1") (pintype "passive"))
    )
    (net (code "55") (name "/MCLR") (class "Default")
      (node (ref "J7") (pin "1") (pinfunction "1_1") (pintype "passive"))
      (node (ref "R2") (pin "1") (pinfunction "1_1") (pintype "passive"))
      (node (ref "U1") (pin "7") (pinfunction "~{MCLR}_7") (pintype "passive"))
    )
    (net (code "56") (name "/PGC") (class "Default")
      (node (ref "J7") (pin "5") (pinfunction "5_5") (pintype "passive"))
      (node (ref "U1") (pin "17") (pinfunction "PGC/EMUC/AN6/OCFA/RB6_17") (pintype "passive"))
    )
    (net (code "57") (name "/PGD") (class "Default")
      (node (ref "J7") (pin "4") (pinfunction "4_4") (pintype "passive"))
      (node (ref "U1") (pin "18") (pinfunction "PGD/EMUD/AN7/RB7_18") (pintype "passive"))
    )
    (net (code "58") (name "/RESET") (class "Default")
      (node (ref "C5") (pin "2") (pinfunction "2_2") (pintype "passive"))
      (node (ref "D2") (pin "1") (pinfunction "A_1") (pintype "passive"))
      (node (ref "R1") (pin "2") (pinfunction "2_2") (pintype "passive"))
      (node (ref "R2") (pin "2") (pinfunction "2_2") (pintype "passive"))
      (node (ref "U3") (pin "1") (pinfunction "~{RST}_1") (pintype "passive"))
    )
    (net (code "59") (name "/RX") (class "Default")
      (node (ref "J2") (pin "10") (pinfunction "10_10") (pintype "passive"))
      (node (ref "U1") (pin "34") (pinfunction "U1RX/SDI1/RF2_34") (pintype "passive"))
    )
    (net (code "60") (name "/TX") (class "Default")
      (node (ref "J2") (pin "8") (pinfunction "8_8") (pintype "passive"))
      (node (ref "U1") (pin "33") (pinfunction "EMUD3/U1TX/SDO1/RF3_33") (pintype "passive"))
    )
    (net (code "61") (name "/WDI") (class "Default")
      (node (ref "R9") (pin "1") (pinfunction "1_1") (pintype "passive"))
      (node (ref "U3") (pin "4") (pinfunction "WDI_4") (pintype "passive"))
    )
    (net (code "62") (name "GND") (class "Default")
      (node (ref "C1") (pin "2") (pinfunction "2_2") (pintype "passive"))
      (node (ref "C10") (pin "2") (pinfunction "2_2") (pintype "passive"))
      (node (ref "C11") (pin "2") (pinfunction "2_2") (pintype "passive"))
      (node (ref "C12") (pin "2") (pinfunction "2_2") (pintype "passive"))
      (node (ref "C13") (pin "2") (pinfunction "2_2") (pintype "passive"))
      (node (ref "C14") (pin "2") (pinfunction "2_2") (pintype "passive"))
      (node (ref "C15") (pin "2") (pinfunction "2_2") (pintype "passive"))
      (node (ref "C16") (pin "2") (pinfunction "2_2") (pintype "passive"))
      (node (ref "C17") (pin "2") (pinfunction "2_2") (pintype "passive"))
      (node (ref "C18") (pin "2") (pinfunction "2_2") (pintype "passive"))
      (node (ref "C19") (pin "2") (pinfunction "2_2") (pintype "passive"))
      (node (ref "C2") (pin "2") (pinfunction "2_2") (pintype "passive"))
      (node (ref "C20") (pin "2") (pinfunction "2_2") (pintype "passive"))
      (node (ref "C21") (pin "2") (pinfunction "2_2") (pintype "passive"))
      (node (ref "C22") (pin "2") (pinfunction "2_2") (pintype "passive"))
      (node (ref "C23") (pin "1") (pinfunction "1_1") (pintype "passive"))
      (node (ref "C24") (pin "1") (pinfunction "1_1") (pintype "passive"))
      (node (ref "C3") (pin "2") (pinfunction "2_2") (pintype "passive"))
      (node (ref "C4") (pin "2") (pinfunction "2_2") (pintype "passive"))
      (node (ref "C5") (pin "1") (pinfunction "1_1") (pintype "passive"))
      (node (ref "C6") (pin "2") (pinfunction "2_2") (pintype "passive"))
      (node (ref "C7") (pin "2") (pinfunction "2_2") (pintype "passive"))
      (node (ref "C8") (pin "1") (pinfunction "1_1") (pintype "passive"))
      (node (ref "C9") (pin "1") (pinfunction "1_1") (pintype "passive"))
      (node (ref "D11") (pin "1") (pinfunction "A_1") (pintype "passive"))
      (node (ref "D12") (pin "1") (pinfunction "A_1") (pintype "passive"))
      (node (ref "D13") (pin "1") (pinfunction "A_1") (pintype "passive"))
      (node (ref "D14") (pin "1") (pinfunction "A_1") (pintype "passive"))
      (node (ref "D4") (pin "1") (pinfunction "A_1") (pintype "passive"))
      (node (ref "D5") (pin "1") (pinfunction "A_1") (pintype "passive"))
      (node (ref "D6") (pin "1") (pinfunction "A_1") (pintype "passive"))
      (node (ref "D7") (pin "1") (pinfunction "A_1") (pintype "passive"))
      (node (ref "J1") (pin "14") (pinfunction "14_14") (pintype "passive"))
      (node (ref "J2") (pin "12") (pinfunction "12_12") (pintype "passive"))
      (node (ref "J2") (pin "14") (pinfunction "14_14") (pintype "passive"))
      (node (ref "J3") (pin "1") (pinfunction "1_1") (pintype "passive"))
      (node (ref "J4") (pin "1") (pinfunction "1_1") (pintype "passive"))
      (node (ref "J7") (pin "3") (pinfunction "3_3") (pintype "passive"))
      (node (ref "LED1") (pin "2") (pinfunction "K_2") (pintype "passive"))
      (node (ref "Q1") (pin "2") (pinfunction "S_2") (pintype "passive"))
      (node (ref "Q2") (pin "2") (pinfunction "S_2") (pintype "passive"))
      (node (ref "Q3") (pin "2") (pinfunction "S_2") (pintype "passive"))
      (node (ref "Q4") (pin "2") (pinfunction "S_2") (pintype "passive"))
      (node (ref "Q5") (pin "2") (pinfunction "S_2") (pintype "passive"))
      (node (ref "Q6") (pin "2") (pinfunction "S_2") (pintype "passive"))
      (node (ref "Q7") (pin "2") (pinfunction "S_2") (pintype "passive"))
      (node (ref "R11") (pin "2") (pinfunction "2_2") (pintype "passive"))
      (node (ref "R14") (pin "2") (pinfunction "2_2") (pintype "passive"))
      (node (ref "R15") (pin "2") (pinfunction "2_2") (pintype "passive"))
      (node (ref "R18") (pin "2") (pinfunction "2_2") (pintype "passive"))
      (node (ref "R19") (pin "2") (pinfunction "2_2") (pintype "passive"))
      (node (ref "R20") (pin "2") (pinfunction "2_2") (pintype "passive"))
      (node (ref "R26") (pin "2") (pinfunction "2_2") (pintype "passive"))
      (node (ref "R31") (pin "2") (pinfunction "2_2") (pintype "passive"))
      (node (ref "R32") (pin "2") (pinfunction "2_2") (pintype "passive"))
      (node (ref "R39") (pin "2") (pinfunction "2_2") (pintype "passive"))
      (node (ref "R40") (pin "2") (pinfunction "2_2") (pintype "passive"))
      (node (ref "R45") (pin "1") (pinfunction "1_1") (pintype "passive"))
      (node (ref "R46") (pin "1") (pinfunction "1_1") (pintype "passive"))
      (node (ref "R7") (pin "1") (pinfunction "1_1") (pintype "passive"))
      (node (ref "S1") (pin "1") (pintype "passive"))
      (node (ref "U1") (pin "20") (pinfunction "AVSS_20") (pintype "passive"))
      (node (ref "U1") (pin "25") (pinfunction "VSS_25") (pintype "passive"))
      (node (ref "U1") (pin "41") (pinfunction "VSS_41") (pintype "passive"))
      (node (ref "U1") (pin "56") (pinfunction "VSS_56") (pintype "passive"))
      (node (ref "U1") (pin "9") (pinfunction "VSS_9") (pintype "passive"))
      (node (ref "U2") (pin "4") (pinfunction "GND_4") (pintype "power_in"))
      (node (ref "U3") (pin "2") (pinfunction "Vss_2") (pintype "passive"))
      (node (ref "U4") (pin "2") (pinfunction "GND_2") (pintype "power_in"))
      (node (ref "U5") (pin "2") (pinfunction "GND_2") (pintype "power_in"))
    )
    (net (code "63") (name "Net-(C23-Pad2)") (class "Default")
      (node (ref "C23") (pin "2") (pinfunction "2_2") (pintype "passive"))
      (node (ref "R33") (pin "2") (pinfunction "2_2") (pintype "passive"))
      (node (ref "R41") (pin "2") (pinfunction "2_2") (pintype "passive"))
      (node (ref "R43") (pin "2") (pinfunction "2_2") (pintype "passive"))
    )
    (net (code "64") (name "Net-(C24-Pad2)") (class "Default")
      (node (ref "C24") (pin "2") (pinfunction "2_2") (pintype "passive"))
      (node (ref "R34") (pin "2") (pinfunction "2_2") (pintype "passive"))
      (node (ref "R42") (pin "2") (pinfunction "2_2") (pintype "passive"))
      (node (ref "R44") (pin "2") (pinfunction "2_2") (pintype "passive"))
    )
    (net (code "65") (name "Net-(D3-A)") (class "Default")
      (node (ref "C8") (pin "2") (pinfunction "2_2") (pintype "passive"))
      (node (ref "D3") (pin "1") (pinfunction "A_1") (pintype "passive"))
      (node (ref "R5") (pin "1") (pinfunction "1_1") (pintype "passive"))
      (node (ref "S1") (pin "2") (pintype "passive"))
      (node (ref "U3") (pin "3") (pinfunction "~{MR}_3") (pintype "passive"))
    )
    (net (code "66") (name "Net-(D4-K)") (class "Default")
      (node (ref "D4") (pin "2") (pinfunction "K_2") (pintype "passive"))
      (node (ref "L1") (pin "1") (pinfunction "1_1") (pintype "passive"))
      (node (ref "U2") (pin "2") (pinfunction "SWE_2") (pintype "open_emitter"))
    )
    (net (code "67") (name "Net-(D8-K)") (class "Default")
      (node (ref "D8") (pin "2") (pinfunction "K_2") (pintype "passive"))
      (node (ref "R21") (pin "2") (pinfunction "2_2") (pintype "passive"))
    )
    (net (code "68") (name "Net-(D9-K)") (class "Default")
      (node (ref "D9") (pin "2") (pinfunction "K_2") (pintype "passive"))
      (node (ref "R22") (pin "2") (pinfunction "2_2") (pintype "passive"))
    )
    (net (code "69") (name "Net-(D10-K)") (class "Default")
      (node (ref "D10") (pin "2") (pinfunction "K_2") (pintype "passive"))
      (node (ref "R23") (pin "2") (pinfunction "2_2") (pintype "passive"))
    )
    (net (code "70") (name "Net-(LED1-A)") (class "Default")
      (node (ref "LED1") (pin "1") (pinfunction "A_1") (pintype "passive"))
      (node (ref "R4") (pin "2") (pinfunction "2_2") (pintype "passive"))
    )
    (net (code "71") (name "Net-(LED2-K)") (class "Default")
      (node (ref "LED2") (pin "2") (pinfunction "K_2") (pintype "passive"))
      (node (ref "R10") (pin "1") (pinfunction "1_1") (pintype "passive"))
    )
    (net (code "72") (name "Net-(LED3-K)") (class "Default")
      (node (ref "LED3") (pin "2") (pinfunction "K_2") (pintype "passive"))
      (node (ref "R11") (pin "1") (pinfunction "1_1") (pintype "passive"))
    )
    (net (code "73") (name "Net-(LED4-K)") (class "Default")
      (node (ref "LED4") (pin "2") (pinfunction "K_2") (pintype "passive"))
      (node (ref "R16") (pin "1") (pinfunction "1_1") (pintype "passive"))
    )
    (net (code "74") (name "Net-(LED5-K)") (class "Default")
      (node (ref "LED5") (pin "2") (pinfunction "K_2") (pintype "passive"))
      (node (ref "R17") (pin "1") (pinfunction "1_1") (pintype "passive"))
    )
    (net (code "75") (name "Net-(Q1-G)") (class "Default")
      (node (ref "Q1") (pin "3") (pinfunction "G_3") (pintype "passive"))
      (node (ref "R3") (pin "2") (pinfunction "2_2") (pintype "passive"))
    )
    (net (code "76") (name "Net-(Q3-D)") (class "Default")
      (node (ref "Q3") (pin "1") (pinfunction "D_1") (pintype "passive"))
      (node (ref "R21") (pin "1") (pinfunction "1_1") (pintype "passive"))
      (node (ref "R22") (pin "1") (pinfunction "1_1") (pintype "passive"))
      (node (ref "R23") (pin "1") (pinfunction "1_1") (pintype "passive"))
    )
    (net (code "77") (name "Net-(U1-OSC1{slash}CLKI)") (class "Default")
      (node (ref "C10") (pin "1") (pinfunction "1_1") (pintype "passive"))
      (node (ref "U1") (pin "39") (pinfunction "OSC1/CLKI_39") (pintype "passive"))
      (node (ref "Y1") (pin "2") (pinfunction "OSC2_2") (pintype "passive"))
    )
    (net (code "78") (name "Net-(U1-OSC2{slash}CLKO{slash}RC15)") (class "Default")
      (node (ref "C11") (pin "1") (pinfunction "1_1") (pintype "passive"))
      (node (ref "U1") (pin "40") (pinfunction "OSC2/CLKO/RC15_40") (pintype "passive"))
      (node (ref "Y1") (pin "1") (pinfunction "OSC1_1") (pintype "passive"))
    )
    (net (code "79") (name "Net-(U1-SCL{slash}RG2)") (class "Default")
      (node (ref "R10") (pin "2") (pinfunction "2_2") (pintype "passive"))
      (node (ref "U1") (pin "37") (pinfunction "SCL/RG2_37") (pintype "passive"))
    )
    (net (code "80") (name "Net-(U1-~{SS2}{slash}CN11{slash}RG9)") (class "Default")
      (node (ref "R9") (pin "2") (pinfunction "2_2") (pintype "passive"))
      (node (ref "U1") (pin "8") (pinfunction "~{SS2}/CN11/RG9_8") (pintype "passive"))
    )
    (net (code "81") (name "Net-(U2--VIN)") (class "Default")
      (node (ref "R6") (pin "2") (pinfunction "2_2") (pintype "passive"))
      (node (ref "R7") (pin "2") (pinfunction "2_2") (pintype "passive"))
      (node (ref "U2") (pin "5") (pinfunction "-VIN_5") (pintype "input"))
    )
    (net (code "82") (name "Net-(U2-DRVC)") (class "Default")
      (node (ref "R8") (pin "1") (pinfunction "1_1") (pintype "passive"))
      (node (ref "U2") (pin "1") (pinfunction "SWC_1") (pintype "open_collector"))
      (node (ref "U2") (pin "7") (pinfunction "IPK_7") (pintype "passive"))
      (node (ref "U2") (pin "8") (pinfunction "DRVC_8") (pintype "open_collector"))
    )
    (net (code "83") (name "Net-(U2-TCAP)") (class "Default")
      (node (ref "C9") (pin "2") (pinfunction "2_2") (pintype "passive"))
      (node (ref "U2") (pin "3") (pinfunction "TCAP_3") (pintype "passive"))
    )
    (net (code "84") (name "Net-(U4-RS)") (class "Default")
      (node (ref "R31") (pin "1") (pinfunction "1_1") (pintype "passive"))
      (node (ref "U4") (pin "8") (pinfunction "RS_8") (pintype "passive"))
    )
    (net (code "85") (name "Net-(U4-VREF)") (class "Default")
      (node (ref "R33") (pin "1") (pinfunction "1_1") (pintype "passive"))
      (node (ref "U4") (pin "5") (pinfunction "VREF_5") (pintype "output"))
    )
    (net (code "86") (name "Net-(U5-RS)") (class "Default")
      (node (ref "R32") (pin "1") (pinfunction "1_1") (pintype "passive"))
      (node (ref "U5") (pin "8") (pinfunction "RS_8") (pintype "passive"))
    )
    (net (code "87") (name "Net-(U5-VREF)") (class "Default")
      (node (ref "R34") (pin "1") (pinfunction "1_1") (pintype "passive"))
      (node (ref "U5") (pin "5") (pinfunction "VREF_5") (pintype "output"))
    )
    (net (code "88") (name "unconnected-(U1-COFS{slash}RG15-Pad1)") (class "Default")
      (node (ref "U1") (pin "1") (pinfunction "COFS/RG15_1") (pintype "passive"))
    )
    (net (code "89") (name "unconnected-(U1-CSCK{slash}RG14-Pad62)") (class "Default")
      (node (ref "U1") (pin "62") (pinfunction "CSCK/RG14_62") (pintype "passive"))
    )
    (net (code "90") (name "unconnected-(U1-CSDI{slash}RG12-Pad63)") (class "Default")
      (node (ref "U1") (pin "63") (pinfunction "CSDI/RG12_63") (pintype "passive"))
    )
    (net (code "91") (name "unconnected-(U1-CSDO{slash}RG13-Pad64)") (class "Default")
      (node (ref "U1") (pin "64") (pinfunction "CSDO/RG13_64") (pintype "passive"))
    )
    (net (code "92") (name "unconnected-(U1-EMUC3{slash}SCK1{slash}INT0{slash}RF6-Pad35)") (class "Default")
      (node (ref "U1") (pin "35") (pinfunction "EMUC3/SCK1/INT0/RF6_35") (pintype "passive"))
    )
    (net (code "93") (name "unconnected-(U1-SCK2{slash}CN8{slash}RG6-Pad4)") (class "Default")
      (node (ref "U1") (pin "4") (pinfunction "SCK2/CN8/RG6_4") (pintype "passive"))
    )
    (net (code "94") (name "unconnected-(U1-SDA{slash}RG3-Pad36)") (class "Default")
      (node (ref "U1") (pin "36") (pinfunction "SDA/RG3_36") (pintype "passive"))
    )
    (net (code "95") (name "unconnected-(U1-SDI2{slash}CN9{slash}RG7-Pad5)") (class "Default")
      (node (ref "U1") (pin "5") (pinfunction "SDI2/CN9/RG7_5") (pintype "passive"))
    )
    (net (code "96") (name "unconnected-(U1-SDO2{slash}CN10{slash}RG8-Pad6)") (class "Default")
      (node (ref "U1") (pin "6") (pinfunction "SDO2/CN10/RG8_6") (pintype "passive"))
    )
    (net (code "97") (name "unconnected-(U1-T2CK{slash}RC1-Pad2)") (class "Default")
      (node (ref "U1") (pin "2") (pinfunction "T2CK/RC1_2") (pintype "passive"))
    )
    (net (code "98") (name "unconnected-(U1-T3CK{slash}RC2-Pad3)") (class "Default")
      (node (ref "U1") (pin "3") (pinfunction "T3CK/RC2_3") (pintype "passive"))
    )
  )
)
